# Sheet1_1.net
KiCad netlist of a schematic drawn in Altium Designer
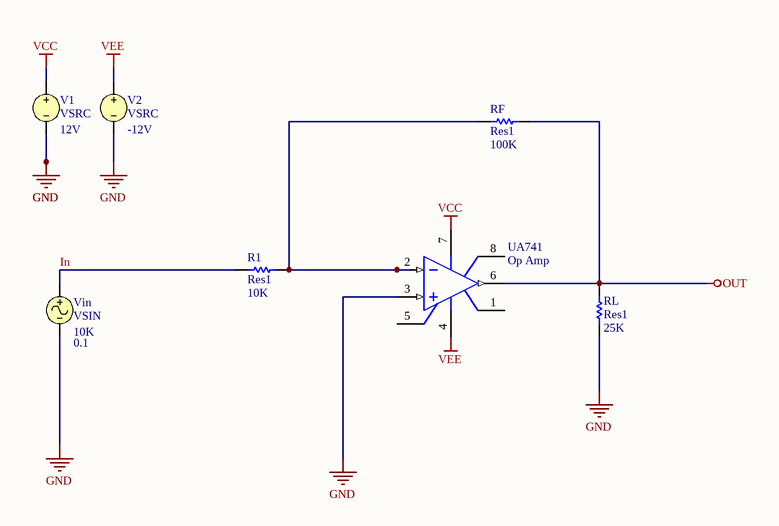
[diagram p0: Sheet1(1).SchDoc]

(export (version "E")
  (design (tool "Eeschema 10.0.6"))
  (components
    (comp (ref "R1")
      (value "Res1")
      (footprint "AXIAL-0.3")
      (description "Resistor")
      (fields (field (name "ALTIUM_VALUE") "10K") (field (name "PUBLISHER") "Altium Limited"))
      (libsource (lib "Miscellaneous Devices") (part "Res1"))
    )
    (comp (ref "RF")
      (value "Res1")
      (footprint "AXIAL-0.3")
      (description "Resistor")
      (fields (field (name "ALTIUM_VALUE") "100K") (field (name "PUBLISHER") "Altium Limited"))
      (libsource (lib "Miscellaneous Devices") (part "Res1"))
    )
    (comp (ref "RL")
      (value "Res1")
      (footprint "AXIAL-0.3")
      (description "Resistor")
      (fields (field (name "ALTIUM_VALUE") "25K") (field (name "PUBLISHER") "Altium Limited"))
      (libsource (lib "Miscellaneous Devices") (part "Res1"))
    )
    (comp (ref "UA741")
      (value "Op Amp")
      (footprint "H-08A")
      (description "FET Operational Amplifier")
      (fields (field (name "PUBLISHER") "Altium Limited"))
      (libsource (lib "Miscellaneous Devices") (part "Op Amp"))
    )
    (comp (ref "V1")
      (value "VSRC")
      (description "Voltage Source")
      (fields (field (name "AMPLITUDE") "12V") (field (name "PUBLISHER") "Altium Limited"))
      (libsource (lib "Simulation Sources") (part "VSRC"))
    )
    (comp (ref "V2")
      (value "VSRC")
      (description "Voltage Source")
      (fields (field (name "AMPLITUDE") "-12V") (field (name "PUBLISHER") "Altium Limited"))
      (libsource (lib "Simulation Sources") (part "VSRC"))
    )
    (comp (ref "Vin")
      (value "VSIN")
      (description "Sinusoidal Voltage Source")
      (fields
        (field (name "FREQUENCY") "10K")
        (field (name "AMPLITUDE") "0.1")
        (field (name "PUBLISHER") "Altium Limited")
      )
      (libsource (lib "Simulation Sources") (part "VSIN"))
    )
  )
  (nets
    (net (code "1") (name "/In") (class "Default")
      (node (ref "R1") (pin "1") (pinfunction "1_1") (pintype "passive"))
      (node (ref "Vin") (pin "1") (pinfunction "1_1") (pintype "passive"))
    )
    (net (code "2") (name "GND") (class "Default")
      (node (ref "RL") (pin "1") (pinfunction "1_1") (pintype "passive"))
      (node (ref "UA741") (pin "3") (pinfunction "IN+_3") (pintype "input"))
      (node (ref "V1") (pin "2") (pinfunction "2_2") (pintype "passive"))
      (node (ref "V2") (pin "2") (pinfunction "2_2") (pintype "passive"))
      (node (ref "Vin") (pin "2") (pinfunction "2_2") (pintype "passive"))
    )
    (net (code "3") (name "Net-(UA741-IN-)") (class "Default")
      (node (ref "R1") (pin "2") (pinfunction "2_2") (pintype "passive"))
      (node (ref "RF") (pin "1") (pinfunction "1_1") (pintype "passive"))
      (node (ref "UA741") (pin "2") (pinfunction "IN-_2") (pintype "input"))
    )
    (net (code "4") (name "OUT") (class "Default")
      (node (ref "RF") (pin "2") (pinfunction "2_2") (pintype "passive"))
      (node (ref "RL") (pin "2") (pinfunction "2_2") (pintype "passive"))
      (node (ref "UA741") (pin "6") (pinfunction "OUT_6") (pintype "output"))
    )
    (net (code "5") (name "VCC") (class "Default")
      (node (ref "UA741") (pin "7") (pinfunction "V+_7") (pintype "power_in"))
      (node (ref "V1") (pin "1") (pinfunction "1_1") (pintype "passive"))
    )
    (net (code "6") (name "VEE") (class "Default")
      (node (ref "UA741") (pin "4") (pinfunction "V-_4") (pintype "power_in"))
      (node (ref "V2") (pin "1") (pinfunction "1_1") (pintype "passive"))
    )
    (net (code "7") (name "unconnected-(UA741-OS_NUL-Pad1)") (class "Default")
      (node (ref "UA741") (pin "1") (pinfunction "OS_NUL_1") (pintype "passive"))
    )
    (net (code "8") (name "unconnected-(UA741-OS_NUL-Pad5)") (class "Default")
      (node (ref "UA741") (pin "5") (pinfunction "OS_NUL_5") (pintype "passive"))
    )
    (net (code "9") (name "unconnected-(UA741-TAB-Pad8)") (class "Default")
      (node (ref "UA741") (pin "8") (pinfunction "TAB_8") (pintype "passive"))
    )
  )
)
